# Sheet1.net
KiCad netlist of a schematic drawn in Altium Designer
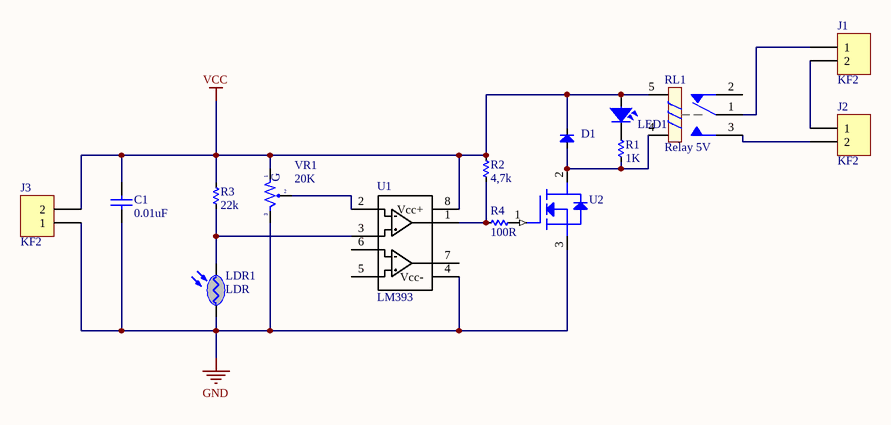
[diagram p0: Sheet1.SchDoc]

(export (version "E")
  (design (tool "Eeschema 10.0.6"))
  (components
    (comp (ref "C1")
      (value "0.01uF")
      (footprint "Cap Non-Pol 3mm")
      (description "Non-polarized Capacitor")
      (fields (field (name "Comment") "Cap Non-pol") (field (name "PUBLISHER") "Altium Limited"))
      (libsource (lib "hphonglib") (part "Cap Non-pol"))
    )
    (comp (ref "D1")
      (value "Diode")
      (footprint "DIO-1A-SMALL")
      (description "Default Diode")
      (fields (field (name "PUBLISHER") "Altium Limited"))
      (libsource (lib "LIBRARY") (part "Diode"))
    )
    (comp (ref "J1")
      (value "KF2")
      (footprint "KF2-3.5")
      (fields
        (field (name "MANUFACTURER") "Würth Elektronik eiSos GmbH")
        (field (name "PARTNO") "691103110002")
        (field (name "CREATED BY") "Karrer Zheng")
      )
      (libsource (lib "LIBRARY") (part "KF2"))
    )
    (comp (ref "J2")
      (value "KF2")
      (footprint "KF2-3.5")
      (fields
        (field (name "MANUFACTURER") "Würth Elektronik eiSos GmbH")
        (field (name "PARTNO") "691103110002")
        (field (name "CREATED BY") "Karrer Zheng")
      )
      (libsource (lib "LIBRARY") (part "KF2"))
    )
    (comp (ref "J3")
      (value "KF2")
      (footprint "KF2-3.5")
      (fields
        (field (name "MANUFACTURER") "Würth Elektronik eiSos GmbH")
        (field (name "PARTNO") "691103110002")
        (field (name "CREATED BY") "Karrer Zheng")
      )
      (libsource (lib "") (part "KF2_1"))
    )
    (comp (ref "LDR1")
      (value "LDR")
      (footprint "CDS")
      (description "Quang Tro")
      (libsource (lib "LIBRARY") (part "LDR"))
    )
    (comp (ref "LED1")
      (value "LED")
      (footprint "LED-3MM-RED")
      (description "LED Single colour Green and Red")
      (libsource (lib "LIBRARY") (part "LED"))
    )
    (comp (ref "R1")
      (value "1K")
      (footprint "RES-1/4W")
      (description "Res")
      (fields
        (field (name "MANUFACTURER") "Generic Components")
        (field (name "PUBLISHER") "Altium Hobart Technology Centre")
      )
      (libsource (lib "LIBRARY") (part "Res"))
    )
    (comp (ref "R2")
      (value "4,7k")
      (footprint "RES-1/4W")
      (description "Res")
      (fields
        (field (name "MANUFACTURER") "Generic Components")
        (field (name "PUBLISHER") "Altium Hobart Technology Centre")
      )
      (libsource (lib "LIBRARY") (part "Res"))
    )
    (comp (ref "R3")
      (value "22k")
      (footprint "RES-1/4W")
      (description "Res")
      (fields
        (field (name "MANUFACTURER") "Generic Components")
        (field (name "PUBLISHER") "Altium Hobart Technology Centre")
      )
      (libsource (lib "LIBRARY") (part "Res"))
    )
    (comp (ref "R4")
      (value "100R")
      (footprint "RES-1/4W")
      (description "Res")
      (fields
        (field (name "MANUFACTURER") "Generic Components")
        (field (name "PUBLISHER") "Altium Hobart Technology Centre")
      )
      (libsource (lib "LIBRARY") (part "Res"))
    )
    (comp (ref "RL1")
      (value "Relay 5V")
      (footprint "RELAY 5")
      (description "Relay SPDT,10A - 12VDC 5 Pin")
      (libsource (lib "LIBRARY") (part "Relay 5"))
    )
    (comp (ref "U1")
      (value "LM393")
      (footprint "DIP8")
      (description "IC DUAL COMPARATOR")
      (libsource (lib "LIBRARY") (part "LM393"))
    )
    (comp (ref "U2")
      (value "IRF540_1")
      (footprint "TO-220N")
      (description "IRF9540 - N-CHANNEL POWER MOSFETS")
      (fields (field (name "PUBLISHER") "Hoang Nguyen"))
      (libsource (lib "hphonglib") (part "IRF540_1"))
    )
    (comp (ref "VR1")
      (value "20K")
      (footprint "VR-S2")
      (description "Var Resistor")
      (libsource (lib "LIBRARY") (part "VR-S"))
    )
  )
  (nets
    (net (code "1") (name "GND") (class "Default")
      (node (ref "C1") (pin "1") (pinfunction "1_1") (pintype "passive"))
      (node (ref "J3") (pin "1") (pinfunction "1_1") (pintype "passive"))
      (node (ref "LDR1") (pin "1") (pinfunction "A_1") (pintype "passive"))
      (node (ref "U1") (pin "4") (pinfunction "Vcc-_4") (pintype "passive"))
      (node (ref "U2") (pin "3") (pinfunction "S_3") (pintype "passive"))
      (node (ref "VR1") (pin "3") (pinfunction "3_3") (pintype "passive"))
    )
    (net (code "2") (name "Net-(D1-A)") (class "Default")
      (node (ref "D1") (pin "1") (pinfunction "A_1") (pintype "passive"))
      (node (ref "R1") (pin "1") (pinfunction "1_1") (pintype "passive"))
      (node (ref "RL1") (pin "4") (pinfunction "4_4") (pintype "passive"))
      (node (ref "U2") (pin "2") (pinfunction "D_2") (pintype "passive"))
    )
    (net (code "3") (name "Net-(J1-Pad1)") (class "Default")
      (node (ref "J1") (pin "1") (pinfunction "1_1") (pintype "passive"))
      (node (ref "RL1") (pin "1") (pinfunction "1_1") (pintype "passive"))
    )
    (net (code "4") (name "Net-(J1-Pad2)") (class "Default")
      (node (ref "J1") (pin "2") (pinfunction "2_2") (pintype "passive"))
      (node (ref "J2") (pin "1") (pinfunction "1_1") (pintype "passive"))
    )
    (net (code "5") (name "Net-(J2-Pad2)") (class "Default")
      (node (ref "J2") (pin "2") (pinfunction "2_2") (pintype "passive"))
      (node (ref "RL1") (pin "3") (pinfunction "3_3") (pintype "passive"))
    )
    (net (code "6") (name "Net-(LDR1-K)") (class "Default")
      (node (ref "LDR1") (pin "2") (pinfunction "K_2") (pintype "passive"))
      (node (ref "R3") (pin "2") (pinfunction "2_2") (pintype "passive"))
      (node (ref "U1") (pin "3") (pintype "passive"))
    )
    (net (code "7") (name "Net-(LED1-Pad2)") (class "Default")
      (node (ref "LED1") (pin "2") (pinfunction "2_2") (pintype "passive"))
      (node (ref "R1") (pin "2") (pinfunction "2_2") (pintype "passive"))
    )
    (net (code "8") (name "Net-(R2-Pad2)") (class "Default")
      (node (ref "R2") (pin "2") (pinfunction "2_2") (pintype "passive"))
      (node (ref "R4") (pin "1") (pinfunction "1_1") (pintype "passive"))
      (node (ref "U1") (pin "1") (pintype "passive"))
    )
    (net (code "9") (name "Net-(U1-Pad2)") (class "Default")
      (node (ref "U1") (pin "2") (pintype "passive"))
      (node (ref "VR1") (pin "2") (pinfunction "2_2") (pintype "passive"))
    )
    (net (code "10") (name "Net-(U2-G)") (class "Default")
      (node (ref "R4") (pin "2") (pinfunction "2_2") (pintype "passive"))
      (node (ref "U2") (pin "1") (pinfunction "G_1") (pintype "input"))
    )
    (net (code "11") (name "VCC") (class "Default")
      (node (ref "C1") (pin "2") (pinfunction "2_2") (pintype "passive"))
      (node (ref "D1") (pin "2") (pinfunction "K_2") (pintype "passive"))
      (node (ref "J3") (pin "2") (pinfunction "2_2") (pintype "passive"))
      (node (ref "LED1") (pin "1") (pinfunction "1_1") (pintype "passive"))
      (node (ref "R2") (pin "1") (pinfunction "1_1") (pintype "passive"))
      (node (ref "R3") (pin "1") (pinfunction "1_1") (pintype "passive"))
      (node (ref "RL1") (pin "5") (pinfunction "5_5") (pintype "passive"))
      (node (ref "U1") (pin "8") (pinfunction "Vcc+_8") (pintype "passive"))
      (node (ref "VR1") (pin "1") (pinfunction "1_1") (pintype "passive"))
    )
    (net (code "12") (name "unconnected-(RL1-Pad2)") (class "Default")
      (node (ref "RL1") (pin "2") (pinfunction "2_2") (pintype "passive"))
    )
    (net (code "13") (name "unconnected-(U1-Pad5)") (class "Default")
      (node (ref "U1") (pin "5") (pintype "passive"))
    )
    (net (code "14") (name "unconnected-(U1-Pad6)") (class "Default")
      (node (ref "U1") (pin "6") (pintype "passive"))
    )
    (net (code "15") (name "unconnected-(U1-Pad7)") (class "Default")
      (node (ref "U1") (pin "7") (pintype "passive"))
    )
  )
)
